# Embedded_Chip.net
KiCad netlist of a schematic drawn in Altium Designer
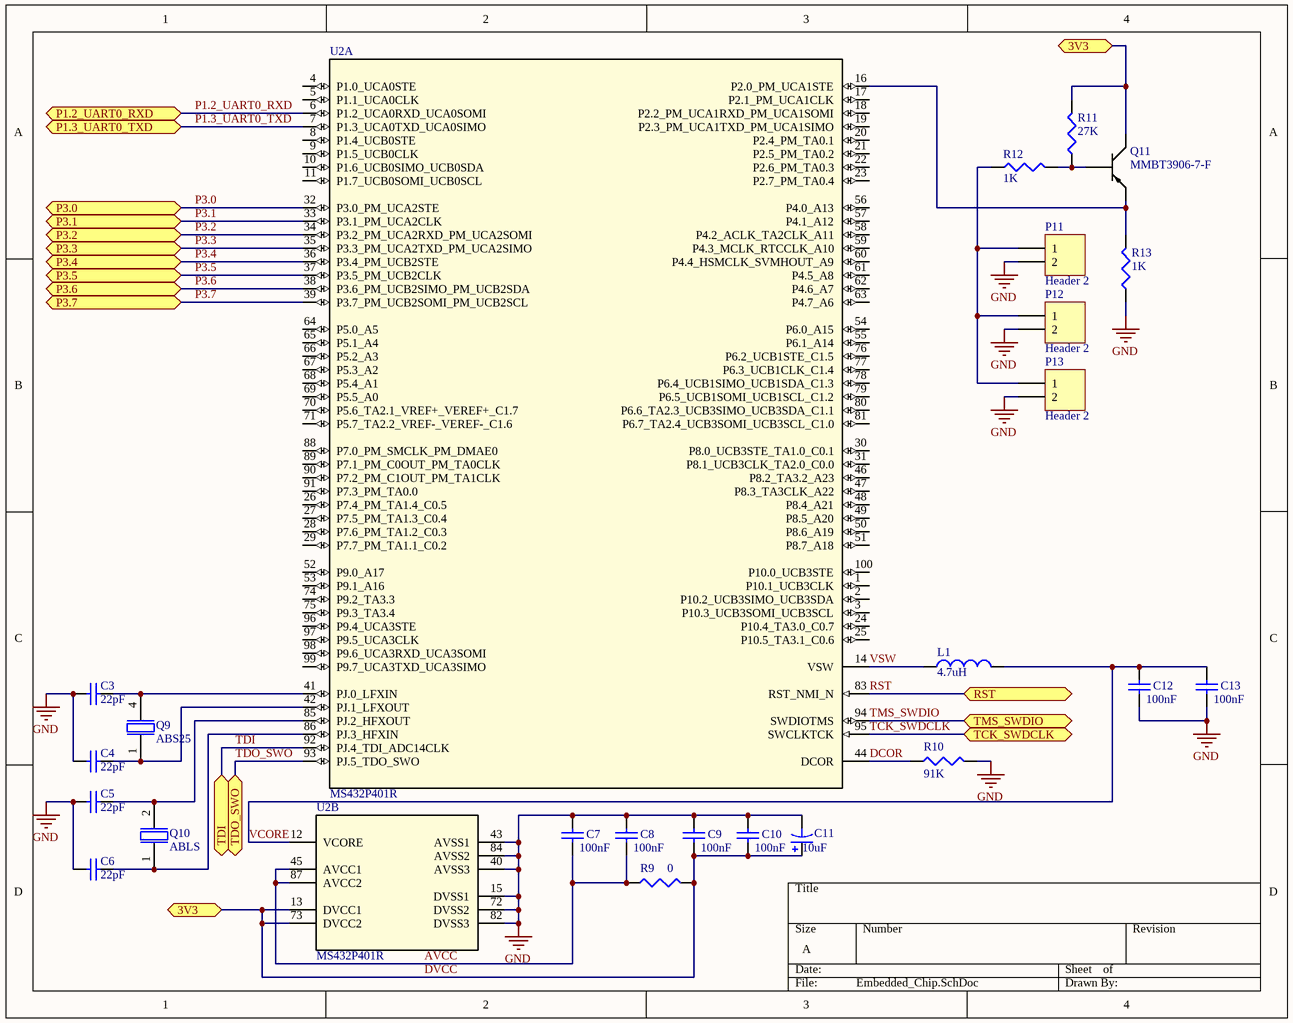
[diagram p0: Embedded_Chip.SchDoc]

(export (version "E")
  (design (tool "Eeschema 10.0.6"))
  (components
    (comp (ref "C3")
      (value "22pF")
      (footprint "C1206")
      (description "Capacitor (Semiconductor SIM Model)")
      (fields (field (name "Comment") "Cap Semi") (field (name "PUBLISHER") "Altium Limited"))
      (libsource (lib "Miscellaneous Devices") (part "Cap Semi"))
    )
    (comp (ref "C4")
      (value "22pF")
      (footprint "C1206")
      (description "Capacitor (Semiconductor SIM Model)")
      (fields (field (name "Comment") "Cap Semi") (field (name "PUBLISHER") "Altium Limited"))
      (libsource (lib "Miscellaneous Devices") (part "Cap Semi"))
    )
    (comp (ref "C5")
      (value "22pF")
      (footprint "C1206")
      (description "Capacitor (Semiconductor SIM Model)")
      (fields (field (name "Comment") "Cap Semi") (field (name "PUBLISHER") "Altium Limited"))
      (libsource (lib "Miscellaneous Devices") (part "Cap Semi"))
    )
    (comp (ref "C6")
      (value "22pF")
      (footprint "C1206")
      (description "Capacitor (Semiconductor SIM Model)")
      (fields (field (name "Comment") "Cap Semi") (field (name "PUBLISHER") "Altium Limited"))
      (libsource (lib "Miscellaneous Devices") (part "Cap Semi"))
    )
    (comp (ref "C7")
      (value "100nF")
      (footprint "C1206")
      (description "Capacitor (Semiconductor SIM Model)")
      (fields (field (name "Comment") "Cap Semi") (field (name "PUBLISHER") "Altium Limited"))
      (libsource (lib "Miscellaneous Devices") (part "Cap Semi"))
    )
    (comp (ref "C8")
      (value "100nF")
      (footprint "C1206")
      (description "Capacitor (Semiconductor SIM Model)")
      (fields (field (name "Comment") "Cap Semi") (field (name "PUBLISHER") "Altium Limited"))
      (libsource (lib "Miscellaneous Devices") (part "Cap Semi"))
    )
    (comp (ref "C9")
      (value "100nF")
      (footprint "C1206")
      (description "Capacitor (Semiconductor SIM Model)")
      (fields (field (name "Comment") "Cap Semi") (field (name "PUBLISHER") "Altium Limited"))
      (libsource (lib "Miscellaneous Devices") (part "Cap Semi"))
    )
    (comp (ref "C10")
      (value "100nF")
      (footprint "C1206")
      (description "Capacitor (Semiconductor SIM Model)")
      (fields (field (name "Comment") "Cap Semi") (field (name "PUBLISHER") "Altium Limited"))
      (libsource (lib "Miscellaneous Devices") (part "Cap Semi"))
    )
    (comp (ref "C11")
      (value "10uF")
      (footprint "CAPAE5043X55M")
      (description "10µF 10V Aluminum Electrolytic Capacitors Radial, Can - SMD 1000 Hrs @ 85°C")
      (fields (field (name "Comment") "Cap Pol3"))
      (libsource (lib "Miscellaneous Devices") (part "Cap Pol3"))
    )
    (comp (ref "C12")
      (value "100nF")
      (footprint "C1206")
      (description "Capacitor (Semiconductor SIM Model)")
      (fields (field (name "Comment") "Cap Semi") (field (name "PUBLISHER") "Altium Limited"))
      (libsource (lib "Miscellaneous Devices") (part "Cap Semi"))
    )
    (comp (ref "C13")
      (value "100nF")
      (footprint "C1206")
      (description "Capacitor (Semiconductor SIM Model)")
      (fields (field (name "Comment") "Cap Semi") (field (name "PUBLISHER") "Altium Limited"))
      (libsource (lib "Miscellaneous Devices") (part "Cap Semi"))
    )
    (comp (ref "L1")
      (value "4.7uH")
      (footprint "0806 (Metric 2016)")
      (description "Inductor")
      (fields (field (name "PUBLISHER") "Altium Limited"))
      (libsource (lib "Miscellaneous Devices") (part "Inductor"))
    )
    (comp (ref "P11")
      (value "Header 2")
      (footprint "HDR1X2")
      (description "Header, 2-Pin")
      (fields (field (name "PUBLISHER") "Altium Limited"))
      (libsource (lib "Miscellaneous Connectors") (part "Header 2"))
    )
    (comp (ref "P12")
      (value "Header 2")
      (footprint "HDR1X2")
      (description "Header, 2-Pin")
      (fields (field (name "PUBLISHER") "Altium Limited"))
      (libsource (lib "Miscellaneous Connectors") (part "Header 2"))
    )
    (comp (ref "P13")
      (value "Header 2")
      (footprint "HDR1X2")
      (description "Header, 2-Pin")
      (fields (field (name "PUBLISHER") "Altium Limited"))
      (libsource (lib "Miscellaneous Connectors") (part "Header 2"))
    )
    (comp (ref "Q9")
      (value "ABS25")
      (footprint "ABS25")
      (description "32.768 kHz Low Frequency SMD Crystal")
      (libsource (lib "Pneumatics_Board_Library") (part "ABS25"))
    )
    (comp (ref "Q10")
      (value "ABLS")
      (footprint "ABLS")
      (description "SMD Low Profile Crystal - 3.579545 MHz to 75 MHz")
      (libsource (lib "Pneumatics_Board_Library") (part "ABLS"))
    )
    (comp (ref "Q11")
      (value "MMBT3906-7-F")
      (footprint "MMBT3906-7-F")
      (description "TRANS PNP 40V 0.2A SOT23-3")
      (libsource (lib "Pneumatics_Board_Library") (part "MMBT3906-7-F"))
    )
    (comp (ref "R9")
      (value "0")
      (footprint "J1-0603")
      (description "Resistor")
      (fields (field (name "Comment") "Res3") (field (name "PUBLISHER") "Altium Limited"))
      (libsource (lib "Miscellaneous Devices") (part "Res3"))
    )
    (comp (ref "R10")
      (value "91K")
      (footprint "J1-0603")
      (description "Resistor")
      (fields (field (name "Comment") "Res3") (field (name "PUBLISHER") "Altium Limited"))
      (libsource (lib "Miscellaneous Devices") (part "Res3"))
    )
    (comp (ref "R11")
      (value "27K")
      (footprint "J1-0603")
      (description "Resistor")
      (fields (field (name "Comment") "Res3") (field (name "PUBLISHER") "Altium Limited"))
      (libsource (lib "Miscellaneous Devices") (part "Res3"))
    )
    (comp (ref "R12")
      (value "1K")
      (footprint "J1-0603")
      (description "Resistor")
      (fields (field (name "Comment") "Res3") (field (name "PUBLISHER") "Altium Limited"))
      (libsource (lib "Miscellaneous Devices") (part "Res3"))
    )
    (comp (ref "R13")
      (value "1K")
      (footprint "J1-0603")
      (description "Resistor")
      (fields (field (name "Comment") "Res3") (field (name "PUBLISHER") "Altium Limited"))
      (libsource (lib "Miscellaneous Devices") (part "Res3"))
    )
    (comp (ref "U2")
      (value "MS432P401R")
      (footprint "PZ0100A_M")
      (description "SimpleLink Ultra-Low-Power 32-Bit ARM Cortex-M4F MCU With Precision ADC, 256KB Flash and 64KB RAM")
      (fields (field (name "PARTNUMBER") "XMS432P401RIPZR") (field (name "MANUFACTURER") "Texas Instruments"))
      (libsource (lib "Pneumatics_Board_Library") (part "MS432P401R-IPZR"))
    )
  )
  (nets
    (net (code "1") (name "/AVCC") (class "Default")
      (node (ref "C7") (pin "1") (pinfunction "1_1") (pintype "passive"))
      (node (ref "C8") (pin "1") (pinfunction "1_1") (pintype "passive"))
      (node (ref "R9") (pin "1") (pinfunction "1_1") (pintype "passive"))
      (node (ref "U2") (pin "45") (pinfunction "AVCC1_45") (pintype "power_in"))
      (node (ref "U2") (pin "87") (pinfunction "AVCC2_87") (pintype "power_in"))
    )
    (net (code "2") (name "/DCOR") (class "Default")
      (node (ref "R10") (pin "1") (pinfunction "1_1") (pintype "passive"))
      (node (ref "U2") (pin "44") (pinfunction "DCOR_44") (pintype "passive"))
    )
    (net (code "3") (name "/DVCC") (class "Default")
      (node (ref "C10") (pin "1") (pinfunction "1_1") (pintype "passive"))
      (node (ref "C11") (pin "1") (pinfunction "1_1") (pintype "passive"))
      (node (ref "C9") (pin "1") (pinfunction "1_1") (pintype "passive"))
      (node (ref "Q11") (pin "C") (pinfunction "Collector_C") (pintype "passive"))
      (node (ref "R11") (pin "2") (pinfunction "2_2") (pintype "passive"))
      (node (ref "R9") (pin "2") (pinfunction "2_2") (pintype "passive"))
      (node (ref "U2") (pin "13") (pinfunction "DVCC1_13") (pintype "power_in"))
      (node (ref "U2") (pin "73") (pinfunction "DVCC2_73") (pintype "power_in"))
    )
    (net (code "4") (name "/P1.2_UART0_RXD") (class "Default")
      (node (ref "U2") (pin "6") (pinfunction "P1.2_UCA0RXD_UCA0SOMI_6") (pintype "bidirectional"))
    )
    (net (code "5") (name "/P1.3_UART0_TXD") (class "Default")
      (node (ref "U2") (pin "7") (pinfunction "P1.3_UCA0TXD_UCA0SIMO_7") (pintype "bidirectional"))
    )
    (net (code "6") (name "/P3.0") (class "Default")
      (node (ref "U2") (pin "32") (pinfunction "P3.0_PM_UCA2STE_32") (pintype "bidirectional"))
    )
    (net (code "7") (name "/P3.1") (class "Default")
      (node (ref "U2") (pin "33") (pinfunction "P3.1_PM_UCA2CLK_33") (pintype "bidirectional"))
    )
    (net (code "8") (name "/P3.2") (class "Default")
      (node (ref "U2") (pin "34") (pinfunction "P3.2_PM_UCA2RXD_PM_UCA2SOMI_34") (pintype "bidirectional"))
    )
    (net (code "9") (name "/P3.3") (class "Default")
      (node (ref "U2") (pin "35") (pinfunction "P3.3_PM_UCA2TXD_PM_UCA2SIMO_35") (pintype "bidirectional"))
    )
    (net (code "10") (name "/P3.4") (class "Default")
      (node (ref "U2") (pin "36") (pinfunction "P3.4_PM_UCB2STE_36") (pintype "bidirectional"))
    )
    (net (code "11") (name "/P3.5") (class "Default")
      (node (ref "U2") (pin "37") (pinfunction "P3.5_PM_UCB2CLK_37") (pintype "bidirectional"))
    )
    (net (code "12") (name "/P3.6") (class "Default")
      (node (ref "U2") (pin "38") (pinfunction "P3.6_PM_UCB2SIMO_PM_UCB2SDA_38") (pintype "bidirectional"))
    )
    (net (code "13") (name "/P3.7") (class "Default")
      (node (ref "U2") (pin "39") (pinfunction "P3.7_PM_UCB2SOMI_PM_UCB2SCL_39") (pintype "bidirectional"))
    )
    (net (code "14") (name "/RST") (class "Default")
      (node (ref "U2") (pin "83") (pinfunction "RST_NMI_N_83") (pintype "input"))
    )
    (net (code "15") (name "/TCK_SWDCLK") (class "Default")
      (node (ref "U2") (pin "95") (pinfunction "SWCLKTCK_95") (pintype "input"))
    )
    (net (code "16") (name "/TDI") (class "Default")
      (node (ref "U2") (pin "92") (pinfunction "PJ.4_TDI_ADC14CLK_92") (pintype "bidirectional"))
    )
    (net (code "17") (name "/TDO_SWO") (class "Default")
      (node (ref "U2") (pin "93") (pinfunction "PJ.5_TDO_SWO_93") (pintype "bidirectional"))
    )
    (net (code "18") (name "/TMS_SWDIO") (class "Default")
      (node (ref "U2") (pin "94") (pinfunction "SWDIOTMS_94") (pintype "bidirectional"))
    )
    (net (code "19") (name "/VCORE") (class "Default")
      (node (ref "C12") (pin "2") (pinfunction "2_2") (pintype "passive"))
      (node (ref "C13") (pin "2") (pinfunction "2_2") (pintype "passive"))
      (node (ref "L1") (pin "2") (pinfunction "2_2") (pintype "passive"))
      (node (ref "U2") (pin "12") (pinfunction "VCORE_12") (pintype "power_in"))
    )
    (net (code "20") (name "/VSW") (class "Default")
      (node (ref "L1") (pin "1") (pinfunction "1_1") (pintype "passive"))
      (node (ref "U2") (pin "14") (pinfunction "VSW_14") (pintype "passive"))
    )
    (net (code "21") (name "GND") (class "Default")
      (node (ref "C10") (pin "2") (pinfunction "2_2") (pintype "passive"))
      (node (ref "C11") (pin "2") (pinfunction "2_2") (pintype "passive"))
      (node (ref "C12") (pin "1") (pinfunction "1_1") (pintype "passive"))
      (node (ref "C13") (pin "1") (pinfunction "1_1") (pintype "passive"))
      (node (ref "C3") (pin "1") (pinfunction "1_1") (pintype "passive"))
      (node (ref "C4") (pin "1") (pinfunction "1_1") (pintype "passive"))
      (node (ref "C5") (pin "1") (pinfunction "1_1") (pintype "passive"))
      (node (ref "C6") (pin "1") (pinfunction "1_1") (pintype "passive"))
      (node (ref "C7") (pin "2") (pinfunction "2_2") (pintype "passive"))
      (node (ref "C8") (pin "2") (pinfunction "2_2") (pintype "passive"))
      (node (ref "C9") (pin "2") (pinfunction "2_2") (pintype "passive"))
      (node (ref "P11") (pin "2") (pinfunction "2_2") (pintype "passive"))
      (node (ref "P12") (pin "2") (pinfunction "2_2") (pintype "passive"))
      (node (ref "P13") (pin "2") (pinfunction "2_2") (pintype "passive"))
      (node (ref "R10") (pin "2") (pinfunction "2_2") (pintype "passive"))
      (node (ref "R13") (pin "1") (pinfunction "1_1") (pintype "passive"))
      (node (ref "U2") (pin "15") (pinfunction "DVSS1_15") (pintype "power_in"))
      (node (ref "U2") (pin "40") (pinfunction "AVSS3_40") (pintype "power_in"))
      (node (ref "U2") (pin "43") (pinfunction "AVSS1_43") (pintype "power_in"))
      (node (ref "U2") (pin "72") (pinfunction "DVSS2_72") (pintype "power_in"))
      (node (ref "U2") (pin "82") (pinfunction "DVSS3_82") (pintype "power_in"))
      (node (ref "U2") (pin "84") (pinfunction "AVSS2_84") (pintype "power_in"))
    )
    (net (code "22") (name "Net-(P11-Pad1)") (class "Default")
      (node (ref "P11") (pin "1") (pinfunction "1_1") (pintype "passive"))
      (node (ref "P12") (pin "1") (pinfunction "1_1") (pintype "passive"))
      (node (ref "P13") (pin "1") (pinfunction "1_1") (pintype "passive"))
      (node (ref "R12") (pin "1") (pinfunction "1_1") (pintype "passive"))
    )
    (net (code "23") (name "Net-(Q11-Body)") (class "Default")
      (node (ref "Q11") (pin "B") (pinfunction "Body_B") (pintype "passive"))
      (node (ref "R11") (pin "1") (pinfunction "1_1") (pintype "passive"))
      (node (ref "R12") (pin "2") (pinfunction "2_2") (pintype "passive"))
    )
    (net (code "24") (name "Net-(Q11-Emitter)") (class "Default")
      (node (ref "Q11") (pin "E") (pinfunction "Emitter_E") (pintype "passive"))
      (node (ref "R13") (pin "2") (pinfunction "2_2") (pintype "passive"))
      (node (ref "U2") (pin "16") (pinfunction "P2.0_PM_UCA1STE_16") (pintype "bidirectional"))
    )
    (net (code "25") (name "Net-(U2A-PJ.0_LFXIN)") (class "Default")
      (node (ref "C3") (pin "2") (pinfunction "2_2") (pintype "passive"))
      (node (ref "Q9") (pin "4") (pinfunction "4_4") (pintype "passive"))
      (node (ref "U2") (pin "41") (pinfunction "PJ.0_LFXIN_41") (pintype "bidirectional"))
    )
    (net (code "26") (name "Net-(U2A-PJ.1_LFXOUT)") (class "Default")
      (node (ref "C4") (pin "2") (pinfunction "2_2") (pintype "passive"))
      (node (ref "Q9") (pin "1") (pinfunction "1_1") (pintype "passive"))
      (node (ref "U2") (pin "42") (pinfunction "PJ.1_LFXOUT_42") (pintype "bidirectional"))
    )
    (net (code "27") (name "Net-(U2A-PJ.2_HFXOUT)") (class "Default")
      (node (ref "C5") (pin "2") (pinfunction "2_2") (pintype "passive"))
      (node (ref "Q10") (pin "2") (pinfunction "2_2") (pintype "passive"))
      (node (ref "U2") (pin "85") (pinfunction "PJ.2_HFXOUT_85") (pintype "bidirectional"))
    )
    (net (code "28") (name "Net-(U2A-PJ.3_HFXIN)") (class "Default")
      (node (ref "C6") (pin "2") (pinfunction "2_2") (pintype "passive"))
      (node (ref "Q10") (pin "1") (pinfunction "1_1") (pintype "passive"))
      (node (ref "U2") (pin "86") (pinfunction "PJ.3_HFXIN_86") (pintype "bidirectional"))
    )
    (net (code "29") (name "unconnected-(U2A-P1.0_UCA0STE-Pad4)") (class "Default")
      (node (ref "U2") (pin "4") (pinfunction "P1.0_UCA0STE_4") (pintype "bidirectional"))
    )
    (net (code "30") (name "unconnected-(U2A-P1.1_UCA0CLK-Pad5)") (class "Default")
      (node (ref "U2") (pin "5") (pinfunction "P1.1_UCA0CLK_5") (pintype "bidirectional"))
    )
    (net (code "31") (name "unconnected-(U2A-P1.4_UCB0STE-Pad8)") (class "Default")
      (node (ref "U2") (pin "8") (pinfunction "P1.4_UCB0STE_8") (pintype "bidirectional"))
    )
    (net (code "32") (name "unconnected-(U2A-P1.5_UCB0CLK-Pad9)") (class "Default")
      (node (ref "U2") (pin "9") (pinfunction "P1.5_UCB0CLK_9") (pintype "bidirectional"))
    )
    (net (code "33") (name "unconnected-(U2A-P1.6_UCB0SIMO_UCB0SDA-Pad10)") (class "Default")
      (node (ref "U2") (pin "10") (pinfunction "P1.6_UCB0SIMO_UCB0SDA_10") (pintype "bidirectional"))
    )
    (net (code "34") (name "unconnected-(U2A-P1.7_UCB0SOMI_UCB0SCL-Pad11)") (class "Default")
      (node (ref "U2") (pin "11") (pinfunction "P1.7_UCB0SOMI_UCB0SCL_11") (pintype "bidirectional"))
    )
    (net (code "35") (name "unconnected-(U2A-P2.1_PM_UCA1CLK-Pad17)") (class "Default")
      (node (ref "U2") (pin "17") (pinfunction "P2.1_PM_UCA1CLK_17") (pintype "bidirectional"))
    )
    (net (code "36") (name "unconnected-(U2A-P2.2_PM_UCA1RXD_PM_UCA1SOMI-Pad18)") (class "Default")
      (node (ref "U2") (pin "18") (pinfunction "P2.2_PM_UCA1RXD_PM_UCA1SOMI_18") (pintype "bidirectional"))
    )
    (net (code "37") (name "unconnected-(U2A-P2.3_PM_UCA1TXD_PM_UCA1SIMO-Pad19)") (class "Default")
      (node (ref "U2") (pin "19") (pinfunction "P2.3_PM_UCA1TXD_PM_UCA1SIMO_19") (pintype "bidirectional"))
    )
    (net (code "38") (name "unconnected-(U2A-P2.4_PM_TA0.1-Pad20)") (class "Default")
      (node (ref "U2") (pin "20") (pinfunction "P2.4_PM_TA0.1_20") (pintype "bidirectional"))
    )
    (net (code "39") (name "unconnected-(U2A-P2.5_PM_TA0.2-Pad21)") (class "Default")
      (node (ref "U2") (pin "21") (pinfunction "P2.5_PM_TA0.2_21") (pintype "bidirectional"))
    )
    (net (code "40") (name "unconnected-(U2A-P2.6_PM_TA0.3-Pad22)") (class "Default")
      (node (ref "U2") (pin "22") (pinfunction "P2.6_PM_TA0.3_22") (pintype "bidirectional"))
    )
    (net (code "41") (name "unconnected-(U2A-P2.7_PM_TA0.4-Pad23)") (class "Default")
      (node (ref "U2") (pin "23") (pinfunction "P2.7_PM_TA0.4_23") (pintype "bidirectional"))
    )
    (net (code "42") (name "unconnected-(U2A-P4.0_A13-Pad56)") (class "Default")
      (node (ref "U2") (pin "56") (pinfunction "P4.0_A13_56") (pintype "bidirectional"))
    )
    (net (code "43") (name "unconnected-(U2A-P4.1_A12-Pad57)") (class "Default")
      (node (ref "U2") (pin "57") (pinfunction "P4.1_A12_57") (pintype "bidirectional"))
    )
    (net (code "44") (name "unconnected-(U2A-P4.2_ACLK_TA2CLK_A11-Pad58)") (class "Default")
      (node (ref "U2") (pin "58") (pinfunction "P4.2_ACLK_TA2CLK_A11_58") (pintype "bidirectional"))
    )
    (net (code "45") (name "unconnected-(U2A-P4.3_MCLK_RTCCLK_A10-Pad59)") (class "Default")
      (node (ref "U2") (pin "59") (pinfunction "P4.3_MCLK_RTCCLK_A10_59") (pintype "bidirectional"))
    )
    (net (code "46") (name "unconnected-(U2A-P4.4_HSMCLK_SVMHOUT_A9-Pad60)") (class "Default")
      (node (ref "U2") (pin "60") (pinfunction "P4.4_HSMCLK_SVMHOUT_A9_60") (pintype "bidirectional"))
    )
    (net (code "47") (name "unconnected-(U2A-P4.5_A8-Pad61)") (class "Default")
      (node (ref "U2") (pin "61") (pinfunction "P4.5_A8_61") (pintype "bidirectional"))
    )
    (net (code "48") (name "unconnected-(U2A-P4.6_A7-Pad62)") (class "Default")
      (node (ref "U2") (pin "62") (pinfunction "P4.6_A7_62") (pintype "bidirectional"))
    )
    (net (code "49") (name "unconnected-(U2A-P4.7_A6-Pad63)") (class "Default")
      (node (ref "U2") (pin "63") (pinfunction "P4.7_A6_63") (pintype "bidirectional"))
    )
    (net (code "50") (name "unconnected-(U2A-P5.0_A5-Pad64)") (class "Default")
      (node (ref "U2") (pin "64") (pinfunction "P5.0_A5_64") (pintype "bidirectional"))
    )
    (net (code "51") (name "unconnected-(U2A-P5.1_A4-Pad65)") (class "Default")
      (node (ref "U2") (pin "65") (pinfunction "P5.1_A4_65") (pintype "bidirectional"))
    )
    (net (code "52") (name "unconnected-(U2A-P5.2_A3-Pad66)") (class "Default")
      (node (ref "U2") (pin "66") (pinfunction "P5.2_A3_66") (pintype "bidirectional"))
    )
    (net (code "53") (name "unconnected-(U2A-P5.3_A2-Pad67)") (class "Default")
      (node (ref "U2") (pin "67") (pinfunction "P5.3_A2_67") (pintype "bidirectional"))
    )
    (net (code "54") (name "unconnected-(U2A-P5.4_A1-Pad68)") (class "Default")
      (node (ref "U2") (pin "68") (pinfunction "P5.4_A1_68") (pintype "bidirectional"))
    )
    (net (code "55") (name "unconnected-(U2A-P5.5_A0-Pad69)") (class "Default")
      (node (ref "U2") (pin "69") (pinfunction "P5.5_A0_69") (pintype "bidirectional"))
    )
    (net (code "56") (name "unconnected-(U2A-P5.6_TA2.1_VREF+_VEREF+_C1.7-Pad70)") (class "Default")
      (node (ref "U2") (pin "70") (pinfunction "P5.6_TA2.1_VREF+_VEREF+_C1.7_70") (pintype "bidirectional"))
    )
    (net (code "57") (name "unconnected-(U2A-P5.7_TA2.2_VREF-_VEREF-_C1.6-Pad71)") (class "Default")
      (node (ref "U2") (pin "71") (pinfunction "P5.7_TA2.2_VREF-_VEREF-_C1.6_71") (pintype "bidirectional"))
    )
    (net (code "58") (name "unconnected-(U2A-P6.0_A15-Pad54)") (class "Default")
      (node (ref "U2") (pin "54") (pinfunction "P6.0_A15_54") (pintype "bidirectional"))
    )
    (net (code "59") (name "unconnected-(U2A-P6.1_A14-Pad55)") (class "Default")
      (node (ref "U2") (pin "55") (pinfunction "P6.1_A14_55") (pintype "bidirectional"))
    )
    (net (code "60") (name "unconnected-(U2A-P6.2_UCB1STE_C1.5-Pad76)") (class "Default")
      (node (ref "U2") (pin "76") (pinfunction "P6.2_UCB1STE_C1.5_76") (pintype "bidirectional"))
    )
    (net (code "61") (name "unconnected-(U2A-P6.3_UCB1CLK_C1.4-Pad77)") (class "Default")
      (node (ref "U2") (pin "77") (pinfunction "P6.3_UCB1CLK_C1.4_77") (pintype "bidirectional"))
    )
    (net (code "62") (name "unconnected-(U2A-P6.4_UCB1SIMO_UCB1SDA_C1.3-Pad78)") (class "Default")
      (node (ref "U2") (pin "78") (pinfunction "P6.4_UCB1SIMO_UCB1SDA_C1.3_78") (pintype "bidirectional"))
    )
    (net (code "63") (name "unconnected-(U2A-P6.5_UCB1SOMI_UCB1SCL_C1.2-Pad79)") (class "Default")
      (node (ref "U2") (pin "79") (pinfunction "P6.5_UCB1SOMI_UCB1SCL_C1.2_79") (pintype "bidirectional"))
    )
    (net (code "64") (name "unconnected-(U2A-P6.6_TA2.3_UCB3SIMO_UCB3SDA_C1.1-Pad80)") (class "Default")
      (node (ref "U2") (pin "80") (pinfunction "P6.6_TA2.3_UCB3SIMO_UCB3SDA_C1.1_80") (pintype "bidirectional"))
    )
    (net (code "65") (name "unconnected-(U2A-P6.7_TA2.4_UCB3SOMI_UCB3SCL_C1.0-Pad81)") (class "Default")
      (node (ref "U2") (pin "81") (pinfunction "P6.7_TA2.4_UCB3SOMI_UCB3SCL_C1.0_81") (pintype "bidirectional"))
    )
    (net (code "66") (name "unconnected-(U2A-P7.0_PM_SMCLK_PM_DMAE0-Pad88)") (class "Default")
      (node (ref "U2") (pin "88") (pinfunction "P7.0_PM_SMCLK_PM_DMAE0_88") (pintype "bidirectional"))
    )
    (net (code "67") (name "unconnected-(U2A-P7.1_PM_C0OUT_PM_TA0CLK-Pad89)") (class "Default")
      (node (ref "U2") (pin "89") (pinfunction "P7.1_PM_C0OUT_PM_TA0CLK_89") (pintype "bidirectional"))
    )
    (net (code "68") (name "unconnected-(U2A-P7.2_PM_C1OUT_PM_TA1CLK-Pad90)") (class "Default")
      (node (ref "U2") (pin "90") (pinfunction "P7.2_PM_C1OUT_PM_TA1CLK_90") (pintype "bidirectional"))
    )
    (net (code "69") (name "unconnected-(U2A-P7.3_PM_TA0.0-Pad91)") (class "Default")
      (node (ref "U2") (pin "91") (pinfunction "P7.3_PM_TA0.0_91") (pintype "bidirectional"))
    )
    (net (code "70") (name "unconnected-(U2A-P7.4_PM_TA1.4_C0.5-Pad26)") (class "Default")
      (node (ref "U2") (pin "26") (pinfunction "P7.4_PM_TA1.4_C0.5_26") (pintype "bidirectional"))
    )
    (net (code "71") (name "unconnected-(U2A-P7.5_PM_TA1.3_C0.4-Pad27)") (class "Default")
      (node (ref "U2") (pin "27") (pinfunction "P7.5_PM_TA1.3_C0.4_27") (pintype "bidirectional"))
    )
    (net (code "72") (name "unconnected-(U2A-P7.6_PM_TA1.2_C0.3-Pad28)") (class "Default")
      (node (ref "U2") (pin "28") (pinfunction "P7.6_PM_TA1.2_C0.3_28") (pintype "bidirectional"))
    )
    (net (code "73") (name "unconnected-(U2A-P7.7_PM_TA1.1_C0.2-Pad29)") (class "Default")
      (node (ref "U2") (pin "29") (pinfunction "P7.7_PM_TA1.1_C0.2_29") (pintype "bidirectional"))
    )
    (net (code "74") (name "unconnected-(U2A-P8.0_UCB3STE_TA1.0_C0.1-Pad30)") (class "Default")
      (node (ref "U2") (pin "30") (pinfunction "P8.0_UCB3STE_TA1.0_C0.1_30") (pintype "bidirectional"))
    )
    (net (code "75") (name "unconnected-(U2A-P8.1_UCB3CLK_TA2.0_C0.0-Pad31)") (class "Default")
      (node (ref "U2") (pin "31") (pinfunction "P8.1_UCB3CLK_TA2.0_C0.0_31") (pintype "bidirectional"))
    )
    (net (code "76") (name "unconnected-(U2A-P8.2_TA3.2_A23-Pad46)") (class "Default")
      (node (ref "U2") (pin "46") (pinfunction "P8.2_TA3.2_A23_46") (pintype "bidirectional"))
    )
    (net (code "77") (name "unconnected-(U2A-P8.3_TA3CLK_A22-Pad47)") (class "Default")
      (node (ref "U2") (pin "47") (pinfunction "P8.3_TA3CLK_A22_47") (pintype "bidirectional"))
    )
    (net (code "78") (name "unconnected-(U2A-P8.4_A21-Pad48)") (class "Default")
      (node (ref "U2") (pin "48") (pinfunction "P8.4_A21_48") (pintype "bidirectional"))
    )
    (net (code "79") (name "unconnected-(U2A-P8.5_A20-Pad49)") (class "Default")
      (node (ref "U2") (pin "49") (pinfunction "P8.5_A20_49") (pintype "bidirectional"))
    )
    (net (code "80") (name "unconnected-(U2A-P8.6_A19-Pad50)") (class "Default")
      (node (ref "U2") (pin "50") (pinfunction "P8.6_A19_50") (pintype "bidirectional"))
    )
    (net (code "81") (name "unconnected-(U2A-P8.7_A18-Pad51)") (class "Default")
      (node (ref "U2") (pin "51") (pinfunction "P8.7_A18_51") (pintype "bidirectional"))
    )
    (net (code "82") (name "unconnected-(U2A-P9.0_A17-Pad52)") (class "Default")
      (node (ref "U2") (pin "52") (pinfunction "P9.0_A17_52") (pintype "bidirectional"))
    )
    (net (code "83") (name "unconnected-(U2A-P9.1_A16-Pad53)") (class "Default")
      (node (ref "U2") (pin "53") (pinfunction "P9.1_A16_53") (pintype "bidirectional"))
    )
    (net (code "84") (name "unconnected-(U2A-P9.2_TA3.3-Pad74)") (class "Default")
      (node (ref "U2") (pin "74") (pinfunction "P9.2_TA3.3_74") (pintype "bidirectional"))
    )
    (net (code "85") (name "unconnected-(U2A-P9.3_TA3.4-Pad75)") (class "Default")
      (node (ref "U2") (pin "75") (pinfunction "P9.3_TA3.4_75") (pintype "bidirectional"))
    )
    (net (code "86") (name "unconnected-(U2A-P9.4_UCA3STE-Pad96)") (class "Default")
      (node (ref "U2") (pin "96") (pinfunction "P9.4_UCA3STE_96") (pintype "bidirectional"))
    )
    (net (code "87") (name "unconnected-(U2A-P9.5_UCA3CLK-Pad97)") (class "Default")
      (node (ref "U2") (pin "97") (pinfunction "P9.5_UCA3CLK_97") (pintype "bidirectional"))
    )
    (net (code "88") (name "unconnected-(U2A-P9.6_UCA3RXD_UCA3SOMI-Pad98)") (class "Default")
      (node (ref "U2") (pin "98") (pinfunction "P9.6_UCA3RXD_UCA3SOMI_98") (pintype "bidirectional"))
    )
    (net (code "89") (name "unconnected-(U2A-P9.7_UCA3TXD_UCA3SIMO-Pad99)") (class "Default")
      (node (ref "U2") (pin "99") (pinfunction "P9.7_UCA3TXD_UCA3SIMO_99") (pintype "bidirectional"))
    )
    (net (code "90") (name "unconnected-(U2A-P10.0_UCB3STE-Pad100)") (class "Default")
      (node (ref "U2") (pin "100") (pinfunction "P10.0_UCB3STE_100") (pintype "bidirectional"))
    )
    (net (code "91") (name "unconnected-(U2A-P10.1_UCB3CLK-Pad1)") (class "Default")
      (node (ref "U2") (pin "1") (pinfunction "P10.1_UCB3CLK_1") (pintype "bidirectional"))
    )
    (net (code "92") (name "unconnected-(U2A-P10.2_UCB3SIMO_UCB3SDA-Pad2)") (class "Default")
      (node (ref "U2") (pin "2") (pinfunction "P10.2_UCB3SIMO_UCB3SDA_2") (pintype "bidirectional"))
    )
    (net (code "93") (name "unconnected-(U2A-P10.3_UCB3SOMI_UCB3SCL-Pad3)") (class "Default")
      (node (ref "U2") (pin "3") (pinfunction "P10.3_UCB3SOMI_UCB3SCL_3") (pintype "bidirectional"))
    )
    (net (code "94") (name "unconnected-(U2A-P10.4_TA3.0_C0.7-Pad24)") (class "Default")
      (node (ref "U2") (pin "24") (pinfunction "P10.4_TA3.0_C0.7_24") (pintype "bidirectional"))
    )
    (net (code "95") (name "unconnected-(U2A-P10.5_TA3.1_C0.6-Pad25)") (class "Default")
      (node (ref "U2") (pin "25") (pinfunction "P10.5_TA3.1_C0.6_25") (pintype "bidirectional"))
    )
  )
)
